# test.net
KiCad netlist of a schematic drawn in Altium Designer
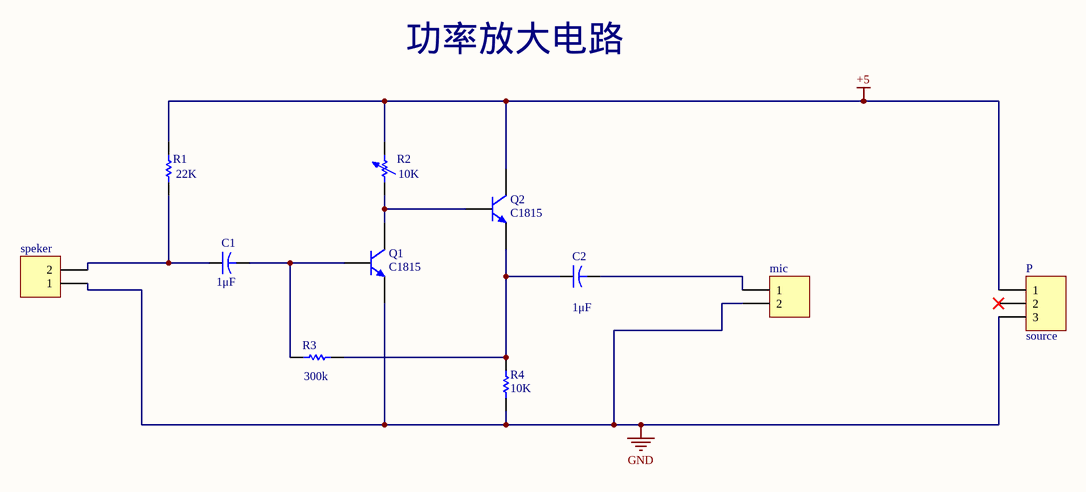
[diagram p0: test.SchDoc]

(export (version "E")
  (design (tool "Eeschema 10.0.6"))
  (components
    (comp (ref "C1")
      (value "1μF")
      (footprint "CAPR5-4X5")
      (description "Capacitor")
      (fields (field (name "Comment") "Cap2") (field (name "PUBLISHER") "Altium Limited"))
      (libsource (lib "Miscellaneous Devices") (part "Cap2"))
    )
    (comp (ref "C2")
      (value "1μF")
      (footprint "CAPR5-4X5")
      (description "Capacitor")
      (fields (field (name "Comment") "Cap2") (field (name "PUBLISHER") "Altium Limited"))
      (libsource (lib "Miscellaneous Devices") (part "Cap2"))
    )
    (comp (ref "mic")
      (value "MHDR1X2")
      (footprint "MHDR1X2")
      (description "Header, 2-Pin")
      (fields (field (name "PUBLISHER") "Altium Limited"))
      (libsource (lib "Miscellaneous Connectors") (part "MHDR1X2"))
    )
    (comp (ref "P")
      (value "source")
      (footprint "MHDR1X3")
      (description "Header, 3-Pin")
      (fields (field (name "PUBLISHER") "Altium Limited"))
      (libsource (lib "Miscellaneous Connectors") (part "MHDR1X3"))
    )
    (comp (ref "Q1")
      (value "C1815")
      (footprint "TO-92A")
      (description "NPN General Purpose Amplifier")
      (fields (field (name "PUBLISHER") "Altium Limited"))
      (libsource (lib "Miscellaneous Devices") (part "2N3904"))
    )
    (comp (ref "Q2")
      (value "C1815")
      (footprint "TO-92A")
      (description "NPN General Purpose Amplifier")
      (fields (field (name "PUBLISHER") "Altium Limited"))
      (libsource (lib "Miscellaneous Devices") (part "2N3904"))
    )
    (comp (ref "R1")
      (value "22K")
      (footprint "AXIAL-0.3")
      (description "Resistor")
      (fields (field (name "Comment") "Res1") (field (name "PUBLISHER") "Altium Limited"))
      (libsource (lib "Miscellaneous Devices") (part "Res1"))
    )
    (comp (ref "R2")
      (value "10K")
      (footprint "AXIAL-0.7")
      (description "Variable Resistor")
      (fields (field (name "Comment") "Res Adj1") (field (name "PUBLISHER") "Altium Limited"))
      (libsource (lib "Miscellaneous Devices") (part "Res Adj1"))
    )
    (comp (ref "R3")
      (value "300k")
      (footprint "AXIAL-0.3")
      (description "Resistor")
      (fields (field (name "Comment") "Res1") (field (name "PUBLISHER") "Altium Limited"))
      (libsource (lib "Miscellaneous Devices") (part "Res1"))
    )
    (comp (ref "R4")
      (value "10K")
      (footprint "AXIAL-0.3")
      (description "Resistor")
      (fields (field (name "Comment") "Res1") (field (name "PUBLISHER") "Altium Limited"))
      (libsource (lib "Miscellaneous Devices") (part "Res1"))
    )
    (comp (ref "speker")
      (value "MHDR1X2")
      (footprint "MHDR1X2")
      (description "Header, 2-Pin")
      (fields (field (name "PUBLISHER") "Altium Limited"))
      (libsource (lib "") (part "MHDR1X2_1"))
    )
  )
  (nets
    (net (code "1") (name "+5") (class "Default")
      (node (ref "P") (pin "1") (pinfunction "1_1") (pintype "passive"))
      (node (ref "Q2") (pin "3") (pinfunction "C_3") (pintype "passive"))
      (node (ref "R1") (pin "1") (pinfunction "1_1") (pintype "passive"))
      (node (ref "R2") (pin "2") (pinfunction "2_2") (pintype "passive"))
    )
    (net (code "2") (name "GND") (class "Default")
      (node (ref "P") (pin "3") (pinfunction "3_3") (pintype "passive"))
      (node (ref "Q1") (pin "1") (pinfunction "E_1") (pintype "passive"))
      (node (ref "R4") (pin "1") (pinfunction "1_1") (pintype "passive"))
      (node (ref "mic") (pin "2") (pinfunction "2_2") (pintype "passive"))
      (node (ref "speker") (pin "1") (pinfunction "1_1") (pintype "passive"))
    )
    (net (code "3") (name "Net-(C1-Pad1)") (class "Default")
      (node (ref "C1") (pin "1") (pinfunction "1_1") (pintype "passive"))
      (node (ref "R1") (pin "2") (pinfunction "2_2") (pintype "passive"))
      (node (ref "speker") (pin "2") (pinfunction "2_2") (pintype "passive"))
    )
    (net (code "4") (name "Net-(C2-Pad2)") (class "Default")
      (node (ref "C2") (pin "2") (pinfunction "2_2") (pintype "passive"))
      (node (ref "mic") (pin "1") (pinfunction "1_1") (pintype "passive"))
    )
    (net (code "5") (name "Net-(Q1-B)") (class "Default")
      (node (ref "C1") (pin "2") (pinfunction "2_2") (pintype "passive"))
      (node (ref "Q1") (pin "2") (pinfunction "B_2") (pintype "passive"))
      (node (ref "R3") (pin "1") (pinfunction "1_1") (pintype "passive"))
    )
    (net (code "6") (name "Net-(Q1-C)") (class "Default")
      (node (ref "Q1") (pin "3") (pinfunction "C_3") (pintype "passive"))
      (node (ref "Q2") (pin "2") (pinfunction "B_2") (pintype "passive"))
      (node (ref "R2") (pin "1") (pinfunction "1_1") (pintype "passive"))
    )
    (net (code "7") (name "Net-(Q2-E)") (class "Default")
      (node (ref "C2") (pin "1") (pinfunction "1_1") (pintype "passive"))
      (node (ref "Q2") (pin "1") (pinfunction "E_1") (pintype "passive"))
      (node (ref "R3") (pin "2") (pinfunction "2_2") (pintype "passive"))
      (node (ref "R4") (pin "2") (pinfunction "2_2") (pintype "passive"))
    )
    (net (code "8") (name "unconnected-(P-Pad2)") (class "Default")
      (node (ref "P") (pin "2") (pinfunction "2_2") (pintype "passive+no_connect"))
    )
  )
)
